# PMSM_500W_Controller_Amp.net
KiCad netlist of a schematic drawn in Altium Designer
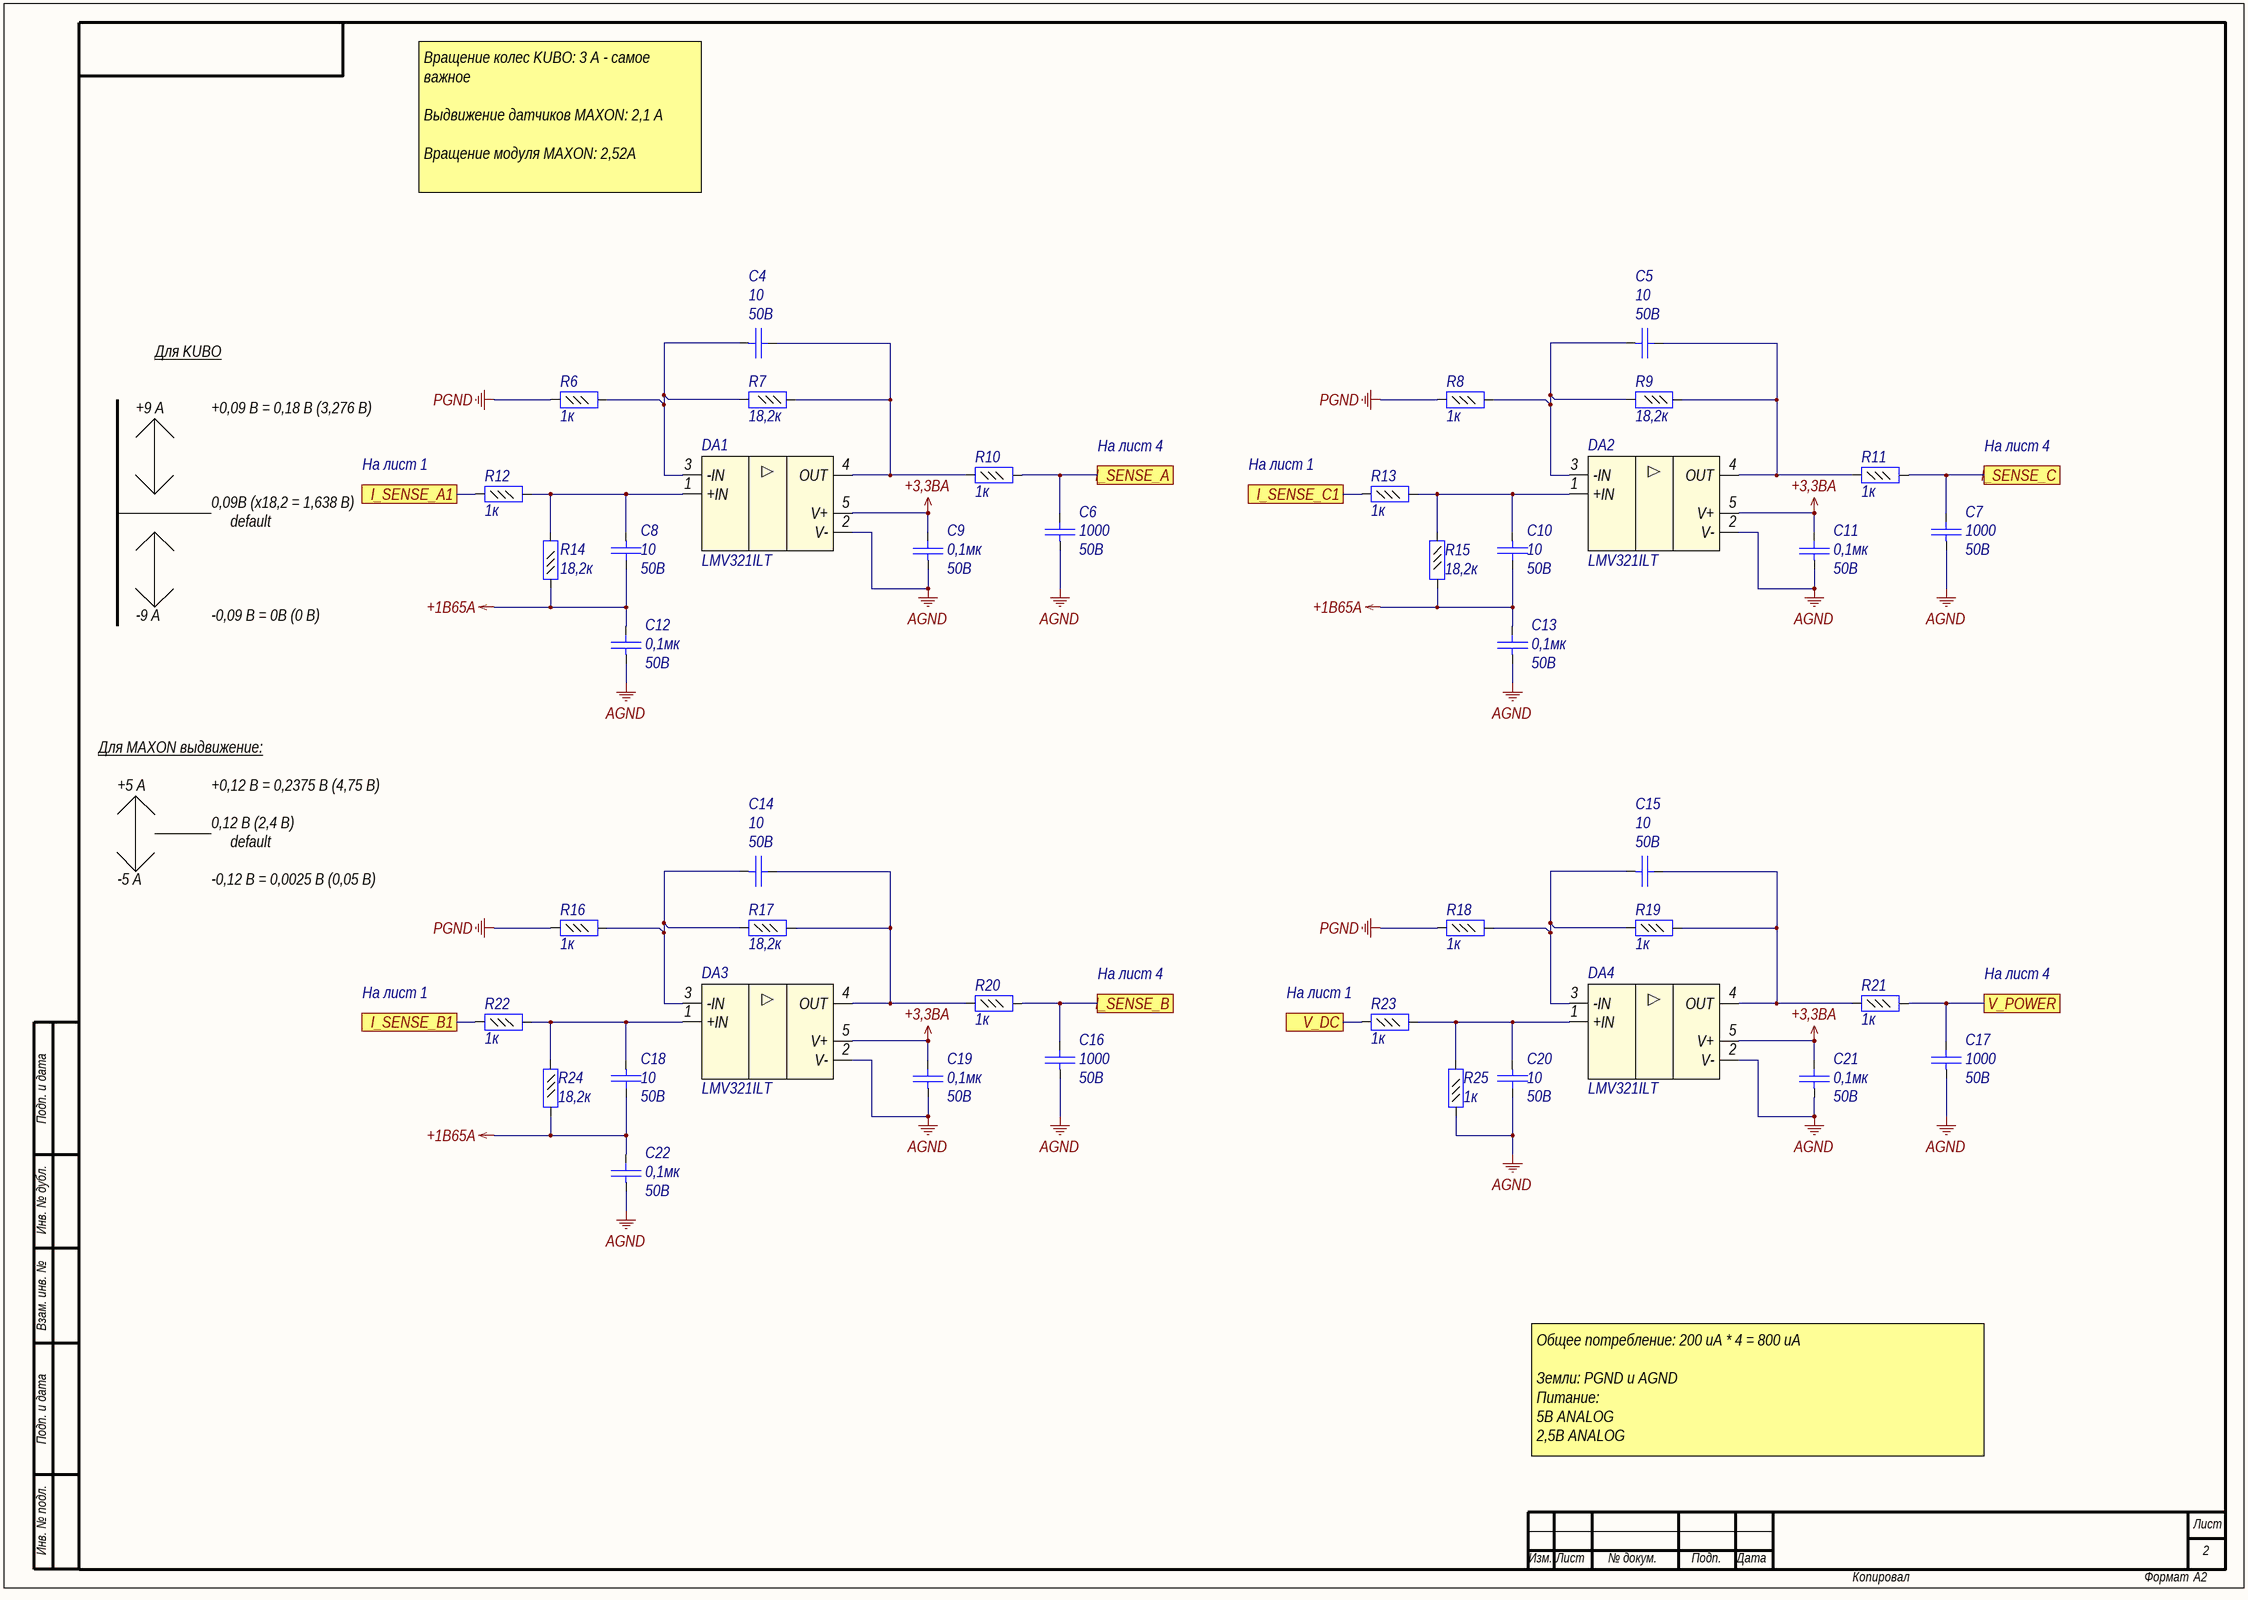
[diagram p0: PMSM_500W_Controller_Amp.SchDoc]

(export (version "E")
  (design (tool "Eeschema 10.0.6"))
  (components
    (comp (ref "C4")
      (value "10")
      (footprint "C0402")
      (description "Конденсатор")
      (fields
        (field (name "VOLTAGE") "50B")
        (field (name "PART NUMBER") "GRM1535C1H100J")
        (field (name "Comment") "Capacitor")
      )
      (libsource (lib "MOP44") (part "Capacitor"))
    )
    (comp (ref "C5")
      (value "10")
      (footprint "C0402")
      (description "Конденсатор")
      (fields
        (field (name "VOLTAGE") "50B")
        (field (name "PART NUMBER") "GRM1535C1H100J")
        (field (name "Comment") "Capacitor")
      )
      (libsource (lib "MOP44") (part "Capacitor"))
    )
    (comp (ref "C6")
      (value "1000")
      (footprint "C0402")
      (description "Конденсатор")
      (fields
        (field (name "VOLTAGE") "50B")
        (field (name "PART NUMBER") "GRM1555C1H102J")
        (field (name "Comment") "Capacitor")
      )
      (libsource (lib "MOP44") (part "Capacitor"))
    )
    (comp (ref "C7")
      (value "1000")
      (footprint "C0402")
      (description "Конденсатор")
      (fields
        (field (name "VOLTAGE") "50B")
        (field (name "PART NUMBER") "GRM1555C1H102J")
        (field (name "Comment") "Capacitor")
      )
      (libsource (lib "MOP44") (part "Capacitor"))
    )
    (comp (ref "C8")
      (value "10")
      (footprint "C0402")
      (description "Конденсатор")
      (fields
        (field (name "VOLTAGE") "50B")
        (field (name "PART NUMBER") "GRM1535C1H100J")
        (field (name "Comment") "Capacitor")
      )
      (libsource (lib "MOP44") (part "Capacitor"))
    )
    (comp (ref "C9")
      (value "0,1мк")
      (footprint "C0402")
      (description "Конденсатор")
      (fields
        (field (name "VOLTAGE") "50В")
        (field (name "PART NUMBER") "GRM155R71H104KE14D")
        (field (name "Comment") "Capacitor")
      )
      (libsource (lib "MOP44") (part "Capacitor"))
    )
    (comp (ref "C10")
      (value "10")
      (footprint "C0402")
      (description "Конденсатор")
      (fields
        (field (name "VOLTAGE") "50B")
        (field (name "PART NUMBER") "GRM1535C1H100J")
        (field (name "Comment") "Capacitor")
      )
      (libsource (lib "MOP44") (part "Capacitor"))
    )
    (comp (ref "C11")
      (value "0,1мк")
      (footprint "C0402")
      (description "Конденсатор")
      (fields
        (field (name "VOLTAGE") "50В")
        (field (name "PART NUMBER") "GRM155R71H104KE14D")
        (field (name "Comment") "Capacitor")
      )
      (libsource (lib "MOP44") (part "Capacitor"))
    )
    (comp (ref "C12")
      (value "0,1мк")
      (footprint "C0402")
      (description "Конденсатор")
      (fields
        (field (name "VOLTAGE") "50В")
        (field (name "PART NUMBER") "GRM155R71H104KE14D")
        (field (name "Comment") "Capacitor")
      )
      (libsource (lib "MOP44") (part "Capacitor"))
    )
    (comp (ref "C13")
      (value "0,1мк")
      (footprint "C0402")
      (description "Конденсатор")
      (fields
        (field (name "VOLTAGE") "50В")
        (field (name "PART NUMBER") "GRM155R71H104KE14D")
        (field (name "Comment") "Capacitor")
      )
      (libsource (lib "MOP44") (part "Capacitor"))
    )
    (comp (ref "C14")
      (value "10")
      (footprint "C0402")
      (description "Конденсатор")
      (fields
        (field (name "VOLTAGE") "50B")
        (field (name "PART NUMBER") "GRM1535C1H100J")
        (field (name "Comment") "Capacitor")
      )
      (libsource (lib "MOP44") (part "Capacitor"))
    )
    (comp (ref "C15")
      (value "10")
      (footprint "C0402")
      (description "Конденсатор")
      (fields
        (field (name "VOLTAGE") "50B")
        (field (name "PART NUMBER") "GRM1535C1H100J")
        (field (name "Comment") "Capacitor")
      )
      (libsource (lib "MOP44") (part "Capacitor"))
    )
    (comp (ref "C16")
      (value "1000")
      (footprint "C0402")
      (description "Конденсатор")
      (fields
        (field (name "VOLTAGE") "50B")
        (field (name "PART NUMBER") "GRM1555C1H102J")
        (field (name "Comment") "Capacitor")
      )
      (libsource (lib "MOP44") (part "Capacitor"))
    )
    (comp (ref "C17")
      (value "1000")
      (footprint "C0402")
      (description "Конденсатор")
      (fields
        (field (name "VOLTAGE") "50B")
        (field (name "PART NUMBER") "GRM1555C1H102J")
        (field (name "Comment") "Capacitor")
      )
      (libsource (lib "MOP44") (part "Capacitor"))
    )
    (comp (ref "C18")
      (value "10")
      (footprint "C0402")
      (description "Конденсатор")
      (fields
        (field (name "VOLTAGE") "50B")
        (field (name "PART NUMBER") "GRM1535C1H100J")
        (field (name "Comment") "Capacitor")
      )
      (libsource (lib "MOP44") (part "Capacitor"))
    )
    (comp (ref "C19")
      (value "0,1мк")
      (footprint "C0402")
      (description "Конденсатор")
      (fields
        (field (name "VOLTAGE") "50В")
        (field (name "PART NUMBER") "GRM155R71H104KE14D")
        (field (name "Comment") "Capacitor")
      )
      (libsource (lib "MOP44") (part "Capacitor"))
    )
    (comp (ref "C20")
      (value "10")
      (footprint "C0402")
      (description "Конденсатор")
      (fields
        (field (name "VOLTAGE") "50B")
        (field (name "PART NUMBER") "GRM1535C1H100J")
        (field (name "Comment") "Capacitor")
      )
      (libsource (lib "MOP44") (part "Capacitor"))
    )
    (comp (ref "C21")
      (value "0,1мк")
      (footprint "C0402")
      (description "Конденсатор")
      (fields
        (field (name "VOLTAGE") "50В")
        (field (name "PART NUMBER") "GRM155R71H104KE14D")
        (field (name "Comment") "Capacitor")
      )
      (libsource (lib "MOP44") (part "Capacitor"))
    )
    (comp (ref "C22")
      (value "0,1мк")
      (footprint "C0402")
      (description "Конденсатор")
      (fields
        (field (name "VOLTAGE") "50В")
        (field (name "PART NUMBER") "GRM155R71H104KE14D")
        (field (name "Comment") "Capacitor")
      )
      (libsource (lib "MOP44") (part "Capacitor"))
    )
    (comp (ref "DA1")
      (value "LMV321ILT")
      (footprint "SOT23-5")
      (description "HIGH-DRIVE OPERATIONAL AMPLIFIERS WITH SHUTDOWN")
      (libsource (lib "MOP44") (part "LMV321ILT"))
    )
    (comp (ref "DA2")
      (value "LMV321ILT")
      (footprint "SOT23-5")
      (description "HIGH-DRIVE OPERATIONAL AMPLIFIERS WITH SHUTDOWN")
      (libsource (lib "MOP44") (part "LMV321ILT"))
    )
    (comp (ref "DA3")
      (value "LMV321ILT")
      (footprint "SOT23-5")
      (description "HIGH-DRIVE OPERATIONAL AMPLIFIERS WITH SHUTDOWN")
      (libsource (lib "MOP44") (part "LMV321ILT"))
    )
    (comp (ref "DA4")
      (value "LMV321ILT")
      (footprint "SOT23-5")
      (description "HIGH-DRIVE OPERATIONAL AMPLIFIERS WITH SHUTDOWN")
      (libsource (lib "MOP44") (part "LMV321ILT"))
    )
    (comp (ref "R6")
      (value "1к")
      (footprint "R0402")
      (description "Резистор")
      (fields (field (name "PART NUMBER") "RC0402FR-071KL") (field (name "POWER") "0,062Вт"))
      (libsource (lib "MOP44") (part "Resistor_0,062Вт"))
    )
    (comp (ref "R7")
      (value "18,2к")
      (footprint "R0402")
      (description "Резистор")
      (fields (field (name "PART NUMBER") "RC0402FR-0718K2L") (field (name "POWER") "0,062Вт"))
      (libsource (lib "") (part "Resistor_0,062Вт_1"))
    )
    (comp (ref "R8")
      (value "1к")
      (footprint "R0402")
      (description "Резистор")
      (fields (field (name "PART NUMBER") "RC0402FR-071KL") (field (name "POWER") "0,062Вт"))
      (libsource (lib "MOP44") (part "Resistor_0,062Вт"))
    )
    (comp (ref "R9")
      (value "18,2к")
      (footprint "R0402")
      (description "Резистор")
      (fields (field (name "PART NUMBER") "RC0402FR-0718K2L") (field (name "POWER") "0,062Вт"))
      (libsource (lib "") (part "Resistor_0,062Вт_1"))
    )
    (comp (ref "R10")
      (value "1к")
      (footprint "R0402")
      (description "Резистор")
      (fields (field (name "PART NUMBER") "RC0402FR-071KL") (field (name "POWER") "0,062Вт"))
      (libsource (lib "MOP44") (part "Resistor_0,062Вт"))
    )
    (comp (ref "R11")
      (value "1к")
      (footprint "R0402")
      (description "Резистор")
      (fields (field (name "PART NUMBER") "RC0402FR-071KL") (field (name "POWER") "0,062Вт"))
      (libsource (lib "MOP44") (part "Resistor_0,062Вт"))
    )
    (comp (ref "R12")
      (value "1к")
      (footprint "R0402")
      (description "Резистор")
      (fields (field (name "PART NUMBER") "RC0402FR-071KL") (field (name "POWER") "0,062Вт"))
      (libsource (lib "MOP44") (part "Resistor_0,062Вт"))
    )
    (comp (ref "R13")
      (value "1к")
      (footprint "R0402")
      (description "Резистор")
      (fields (field (name "PART NUMBER") "RC0402FR-071KL") (field (name "POWER") "0,062Вт"))
      (libsource (lib "MOP44") (part "Resistor_0,062Вт"))
    )
    (comp (ref "R14")
      (value "18,2к")
      (footprint "R0402")
      (description "Резистор")
      (fields (field (name "PART NUMBER") "RC0402FR-0718K2L") (field (name "POWER") "0,062Вт"))
      (libsource (lib "") (part "Resistor_0,062Вт_3"))
    )
    (comp (ref "R15")
      (value "18,2к")
      (footprint "R0402")
      (description "Резистор")
      (fields (field (name "PART NUMBER") "RC0402FR-0718K2L") (field (name "POWER") "0,062Вт"))
      (libsource (lib "") (part "Resistor_0,062Вт_2"))
    )
    (comp (ref "R16")
      (value "1к")
      (footprint "R0402")
      (description "Резистор")
      (fields (field (name "PART NUMBER") "RC0402FR-071KL") (field (name "POWER") "0,062Вт"))
      (libsource (lib "MOP44") (part "Resistor_0,062Вт"))
    )
    (comp (ref "R17")
      (value "18,2к")
      (footprint "R0402")
      (description "Резистор")
      (fields (field (name "PART NUMBER") "RC0402FR-0718K2L") (field (name "POWER") "0,062Вт"))
      (libsource (lib "MOP44") (part "Resistor_0,062Вт"))
    )
    (comp (ref "R18")
      (value "1к")
      (footprint "R0402")
      (description "Резистор")
      (fields (field (name "PART NUMBER") "RC0402FR-071KL") (field (name "POWER") "0,062Вт"))
      (libsource (lib "MOP44") (part "Resistor_0,062Вт"))
    )
    (comp (ref "R19")
      (value "1к")
      (footprint "R0402")
      (description "Резистор")
      (fields (field (name "PART NUMBER") "RC0402FR-071KL") (field (name "POWER") "0,062Вт"))
      (libsource (lib "MOP44") (part "Resistor_0,062Вт"))
    )
    (comp (ref "R20")
      (value "1к")
      (footprint "R0402")
      (description "Резистор")
      (fields (field (name "PART NUMBER") "RC0402FR-071KL") (field (name "POWER") "0,062Вт"))
      (libsource (lib "MOP44") (part "Resistor_0,062Вт"))
    )
    (comp (ref "R21")
      (value "1к")
      (footprint "R0402")
      (description "Резистор")
      (fields (field (name "PART NUMBER") "RC0402FR-071KL") (field (name "POWER") "0,062Вт"))
      (libsource (lib "MOP44") (part "Resistor_0,062Вт"))
    )
    (comp (ref "R22")
      (value "1к")
      (footprint "R0402")
      (description "Резистор")
      (fields (field (name "PART NUMBER") "RC0402FR-071KL") (field (name "POWER") "0,062Вт"))
      (libsource (lib "MOP44") (part "Resistor_0,062Вт"))
    )
    (comp (ref "R23")
      (value "1к")
      (footprint "R0402")
      (description "Резистор")
      (fields (field (name "PART NUMBER") "RC0402FR-071KL") (field (name "POWER") "0,062Вт"))
      (libsource (lib "MOP44") (part "Resistor_0,062Вт"))
    )
    (comp (ref "R24")
      (value "18,2к")
      (footprint "R0402")
      (description "Резистор")
      (fields (field (name "PART NUMBER") "RC0402FR-0718K2L") (field (name "POWER") "0,062Вт"))
      (libsource (lib "") (part "Resistor_0,062Вт_2"))
    )
    (comp (ref "R25")
      (value "1к")
      (footprint "R0402")
      (description "Резистор")
      (fields (field (name "PART NUMBER") "RC0402FR-071KL") (field (name "POWER") "0,062Вт"))
      (libsource (lib "") (part "Resistor_0,062Вт_3"))
    )
  )
  (nets
    (net (code "1") (name "+1B65A") (class "Default")
      (node (ref "C10") (pin "2") (pinfunction "2_2") (pintype "passive"))
      (node (ref "C12") (pin "2") (pinfunction "2_2") (pintype "passive"))
      (node (ref "C13") (pin "2") (pinfunction "2_2") (pintype "passive"))
      (node (ref "C18") (pin "2") (pinfunction "2_2") (pintype "passive"))
      (node (ref "C22") (pin "2") (pinfunction "2_2") (pintype "passive"))
      (node (ref "C8") (pin "2") (pinfunction "2_2") (pintype "passive"))
      (node (ref "R14") (pin "1") (pinfunction "1_1") (pintype "passive"))
      (node (ref "R15") (pin "2") (pinfunction "2_2") (pintype "passive"))
      (node (ref "R24") (pin "2") (pinfunction "2_2") (pintype "passive"))
    )
    (net (code "2") (name "+3,3BA") (class "Default")
      (node (ref "C11") (pin "2") (pinfunction "2_2") (pintype "passive"))
      (node (ref "C19") (pin "2") (pinfunction "2_2") (pintype "passive"))
      (node (ref "C21") (pin "2") (pinfunction "2_2") (pintype "passive"))
      (node (ref "C9") (pin "2") (pinfunction "2_2") (pintype "passive"))
      (node (ref "DA1") (pin "5") (pinfunction "V+_5") (pintype "passive"))
      (node (ref "DA2") (pin "5") (pinfunction "V+_5") (pintype "passive"))
      (node (ref "DA3") (pin "5") (pinfunction "V+_5") (pintype "passive"))
      (node (ref "DA4") (pin "5") (pinfunction "V+_5") (pintype "passive"))
    )
    (net (code "3") (name "/I_SENSE_A") (class "Default")
      (node (ref "C6") (pin "2") (pinfunction "2_2") (pintype "passive"))
      (node (ref "R10") (pin "2") (pinfunction "2_2") (pintype "passive"))
    )
    (net (code "4") (name "/I_SENSE_A1") (class "Default")
      (node (ref "R12") (pin "1") (pinfunction "1_1") (pintype "passive"))
    )
    (net (code "5") (name "/I_SENSE_B") (class "Default")
      (node (ref "C16") (pin "2") (pinfunction "2_2") (pintype "passive"))
      (node (ref "R20") (pin "2") (pinfunction "2_2") (pintype "passive"))
    )
    (net (code "6") (name "/I_SENSE_B1") (class "Default")
      (node (ref "R22") (pin "1") (pinfunction "1_1") (pintype "passive"))
    )
    (net (code "7") (name "/I_SENSE_C") (class "Default")
      (node (ref "C7") (pin "2") (pinfunction "2_2") (pintype "passive"))
      (node (ref "R11") (pin "2") (pinfunction "2_2") (pintype "passive"))
    )
    (net (code "8") (name "/I_SENSE_C1") (class "Default")
      (node (ref "R13") (pin "1") (pinfunction "1_1") (pintype "passive"))
    )
    (net (code "9") (name "/V_DC") (class "Default")
      (node (ref "R23") (pin "1") (pinfunction "1_1") (pintype "passive"))
    )
    (net (code "10") (name "/V_POWER") (class "Default")
      (node (ref "C17") (pin "2") (pinfunction "2_2") (pintype "passive"))
      (node (ref "R21") (pin "2") (pinfunction "2_2") (pintype "passive"))
    )
    (net (code "11") (name "AGND") (class "Default")
      (node (ref "C11") (pin "1") (pinfunction "1_1") (pintype "passive"))
      (node (ref "C12") (pin "1") (pinfunction "1_1") (pintype "passive"))
      (node (ref "C13") (pin "1") (pinfunction "1_1") (pintype "passive"))
      (node (ref "C16") (pin "1") (pinfunction "1_1") (pintype "passive"))
      (node (ref "C17") (pin "1") (pinfunction "1_1") (pintype "passive"))
      (node (ref "C19") (pin "1") (pinfunction "1_1") (pintype "passive"))
      (node (ref "C20") (pin "2") (pinfunction "2_2") (pintype "passive"))
      (node (ref "C21") (pin "1") (pinfunction "1_1") (pintype "passive"))
      (node (ref "C22") (pin "1") (pinfunction "1_1") (pintype "passive"))
      (node (ref "C6") (pin "1") (pinfunction "1_1") (pintype "passive"))
      (node (ref "C7") (pin "1") (pinfunction "1_1") (pintype "passive"))
      (node (ref "C9") (pin "1") (pinfunction "1_1") (pintype "passive"))
      (node (ref "DA1") (pin "2") (pinfunction "V-_2") (pintype "passive"))
      (node (ref "DA2") (pin "2") (pinfunction "V-_2") (pintype "passive"))
      (node (ref "DA3") (pin "2") (pinfunction "V-_2") (pintype "passive"))
      (node (ref "DA4") (pin "2") (pinfunction "V-_2") (pintype "passive"))
      (node (ref "R25") (pin "1") (pinfunction "1_1") (pintype "passive"))
    )
    (net (code "12") (name "Net-(DA1-+IN)") (class "Default")
      (node (ref "C8") (pin "1") (pinfunction "1_1") (pintype "passive"))
      (node (ref "DA1") (pin "1") (pinfunction "+IN_1") (pintype "passive"))
      (node (ref "R12") (pin "2") (pinfunction "2_2") (pintype "passive"))
      (node (ref "R14") (pin "2") (pinfunction "2_2") (pintype "passive"))
    )
    (net (code "13") (name "Net-(DA1--IN)") (class "Default")
      (node (ref "C4") (pin "1") (pinfunction "1_1") (pintype "passive"))
      (node (ref "DA1") (pin "3") (pinfunction "-IN_3") (pintype "passive"))
      (node (ref "R6") (pin "2") (pinfunction "2_2") (pintype "passive"))
      (node (ref "R7") (pin "2") (pinfunction "2_2") (pintype "passive"))
    )
    (net (code "14") (name "Net-(DA1-OUT)") (class "Default")
      (node (ref "C4") (pin "2") (pinfunction "2_2") (pintype "passive"))
      (node (ref "DA1") (pin "4") (pinfunction "OUT_4") (pintype "passive"))
      (node (ref "R10") (pin "1") (pinfunction "1_1") (pintype "passive"))
      (node (ref "R7") (pin "1") (pinfunction "1_1") (pintype "passive"))
    )
    (net (code "15") (name "Net-(DA2-+IN)") (class "Default")
      (node (ref "C10") (pin "1") (pinfunction "1_1") (pintype "passive"))
      (node (ref "DA2") (pin "1") (pinfunction "+IN_1") (pintype "passive"))
      (node (ref "R13") (pin "2") (pinfunction "2_2") (pintype "passive"))
      (node (ref "R15") (pin "1") (pinfunction "1_1") (pintype "passive"))
    )
    (net (code "16") (name "Net-(DA2--IN)") (class "Default")
      (node (ref "C5") (pin "1") (pinfunction "1_1") (pintype "passive"))
      (node (ref "DA2") (pin "3") (pinfunction "-IN_3") (pintype "passive"))
      (node (ref "R8") (pin "2") (pinfunction "2_2") (pintype "passive"))
      (node (ref "R9") (pin "2") (pinfunction "2_2") (pintype "passive"))
    )
    (net (code "17") (name "Net-(DA2-OUT)") (class "Default")
      (node (ref "C5") (pin "2") (pinfunction "2_2") (pintype "passive"))
      (node (ref "DA2") (pin "4") (pinfunction "OUT_4") (pintype "passive"))
      (node (ref "R11") (pin "1") (pinfunction "1_1") (pintype "passive"))
      (node (ref "R9") (pin "1") (pinfunction "1_1") (pintype "passive"))
    )
    (net (code "18") (name "Net-(DA3-+IN)") (class "Default")
      (node (ref "C18") (pin "1") (pinfunction "1_1") (pintype "passive"))
      (node (ref "DA3") (pin "1") (pinfunction "+IN_1") (pintype "passive"))
      (node (ref "R22") (pin "2") (pinfunction "2_2") (pintype "passive"))
      (node (ref "R24") (pin "1") (pinfunction "1_1") (pintype "passive"))
    )
    (net (code "19") (name "Net-(DA3--IN)") (class "Default")
      (node (ref "C14") (pin "1") (pinfunction "1_1") (pintype "passive"))
      (node (ref "DA3") (pin "3") (pinfunction "-IN_3") (pintype "passive"))
      (node (ref "R16") (pin "2") (pinfunction "2_2") (pintype "passive"))
      (node (ref "R17") (pin "1") (pinfunction "1_1") (pintype "passive"))
    )
    (net (code "20") (name "Net-(DA3-OUT)") (class "Default")
      (node (ref "C14") (pin "2") (pinfunction "2_2") (pintype "passive"))
      (node (ref "DA3") (pin "4") (pinfunction "OUT_4") (pintype "passive"))
      (node (ref "R17") (pin "2") (pinfunction "2_2") (pintype "passive"))
      (node (ref "R20") (pin "1") (pinfunction "1_1") (pintype "passive"))
    )
    (net (code "21") (name "Net-(DA4-+IN)") (class "Default")
      (node (ref "C20") (pin "1") (pinfunction "1_1") (pintype "passive"))
      (node (ref "DA4") (pin "1") (pinfunction "+IN_1") (pintype "passive"))
      (node (ref "R23") (pin "2") (pinfunction "2_2") (pintype "passive"))
      (node (ref "R25") (pin "2") (pinfunction "2_2") (pintype "passive"))
    )
    (net (code "22") (name "Net-(DA4--IN)") (class "Default")
      (node (ref "C15") (pin "1") (pinfunction "1_1") (pintype "passive"))
      (node (ref "DA4") (pin "3") (pinfunction "-IN_3") (pintype "passive"))
      (node (ref "R18") (pin "2") (pinfunction "2_2") (pintype "passive"))
      (node (ref "R19") (pin "1") (pinfunction "1_1") (pintype "passive"))
    )
    (net (code "23") (name "Net-(DA4-OUT)") (class "Default")
      (node (ref "C15") (pin "2") (pinfunction "2_2") (pintype "passive"))
      (node (ref "DA4") (pin "4") (pinfunction "OUT_4") (pintype "passive"))
      (node (ref "R19") (pin "2") (pinfunction "2_2") (pintype "passive"))
      (node (ref "R21") (pin "1") (pinfunction "1_1") (pintype "passive"))
    )
    (net (code "24") (name "PGND") (class "Default")
      (node (ref "R16") (pin "1") (pinfunction "1_1") (pintype "passive"))
      (node (ref "R18") (pin "1") (pinfunction "1_1") (pintype "passive"))
      (node (ref "R6") (pin "1") (pinfunction "1_1") (pintype "passive"))
      (node (ref "R8") (pin "1") (pinfunction "1_1") (pintype "passive"))
    )
  )
)
